# M405A.net
KiCad netlist of a schematic drawn in EAGLE
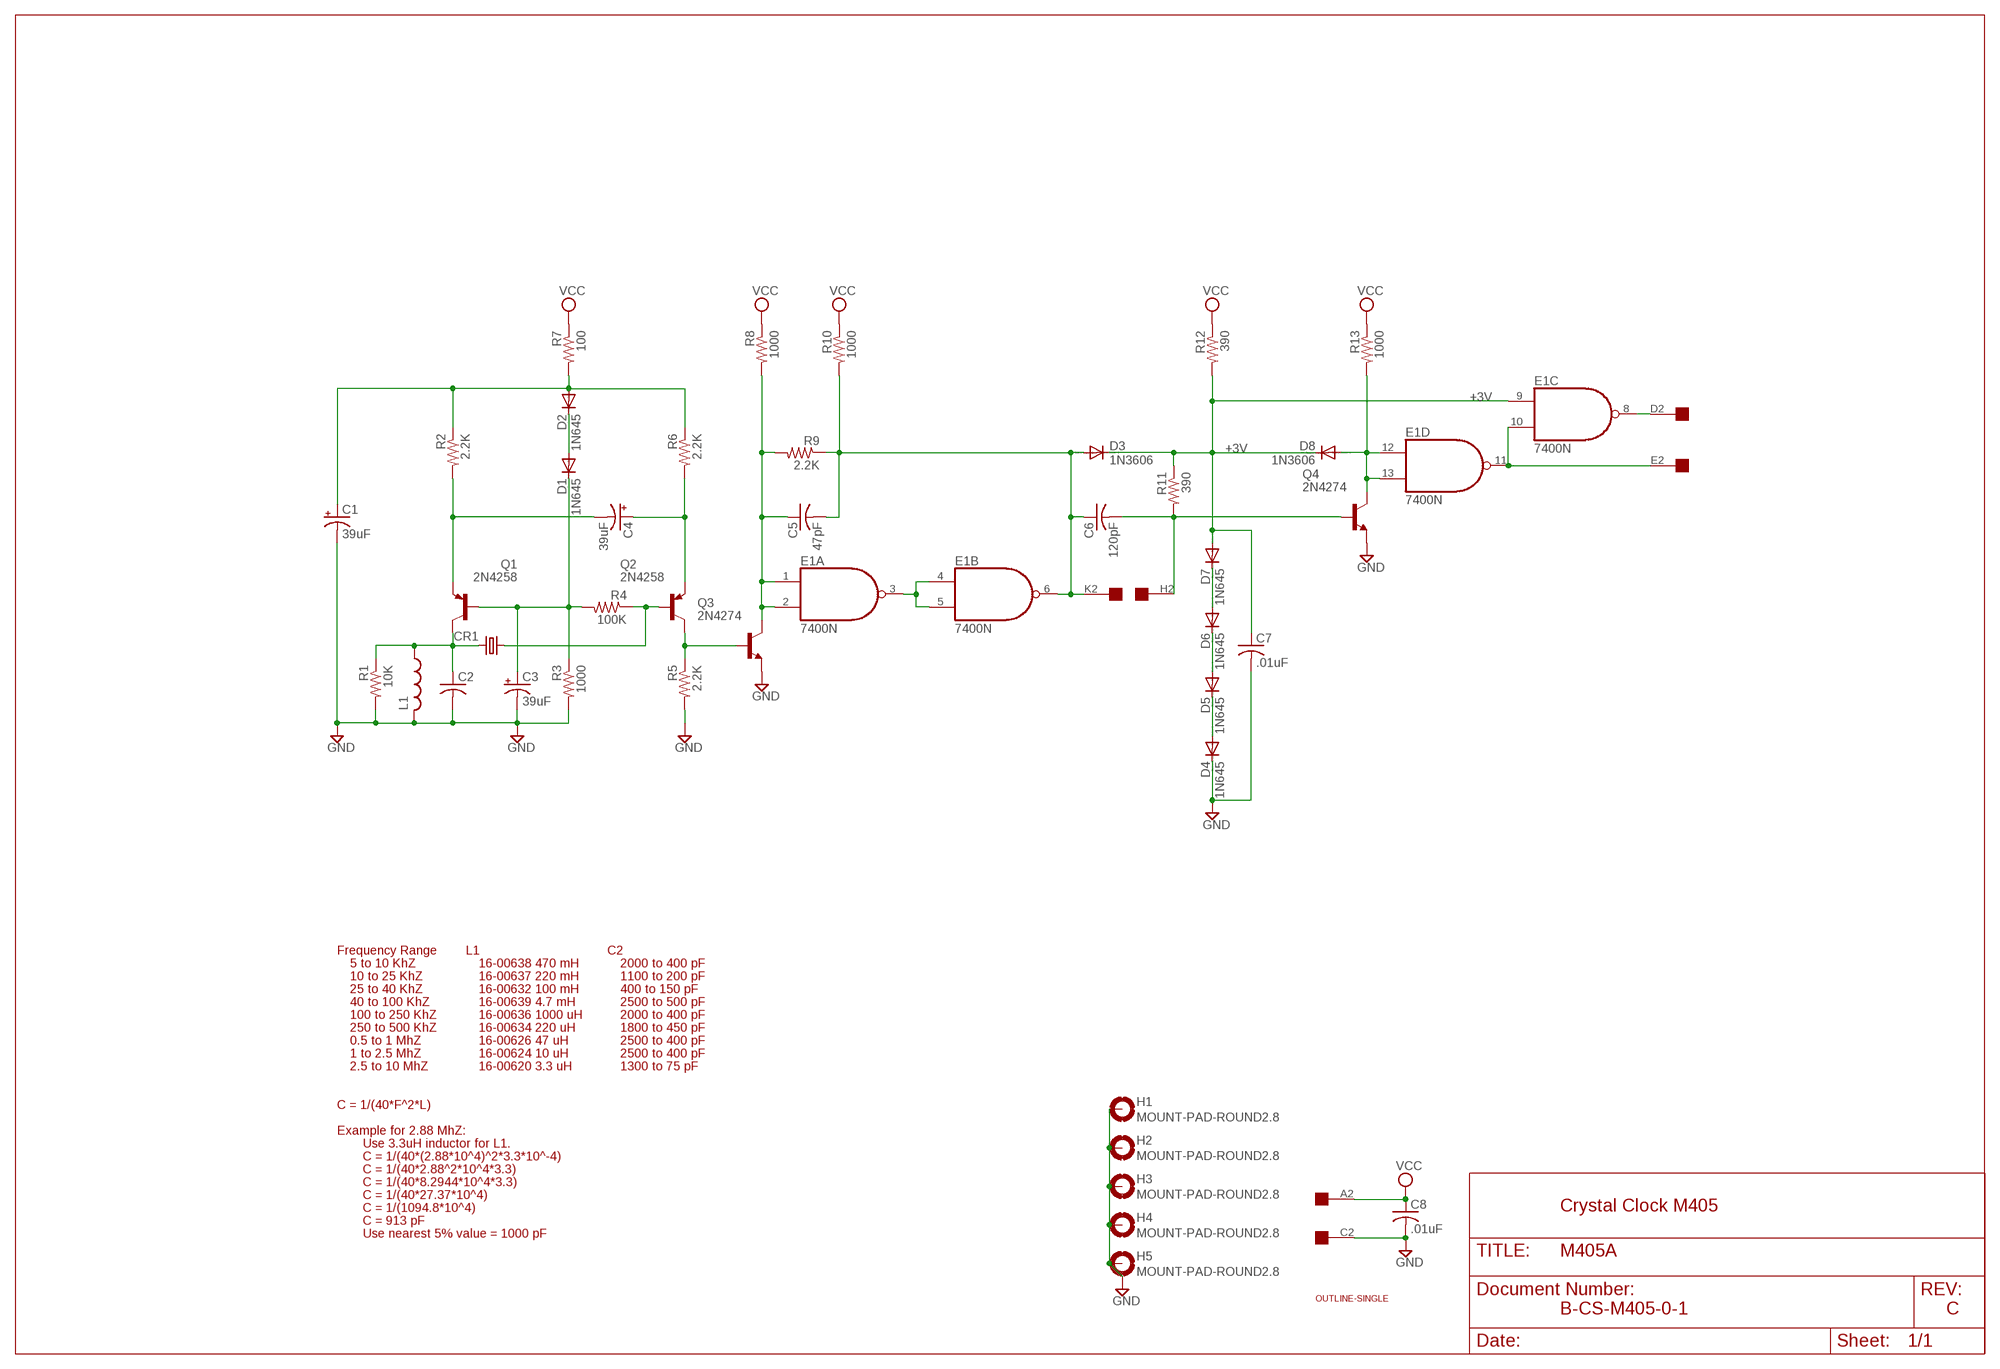
[diagram p0: schematic, sheet 1]

(export (version "E")
  (design (tool "Eeschema 10.0.6"))
  (components
    (comp (ref "C1")
      (value "39uF")
      (footprint "eagle-import:E15-5")
      (libsource (lib "eagle-import") (part "CPOL-USE15-5AXIAL"))
    )
    (comp (ref "C2")
      (value "C-US150-054X183")
      (footprint "eagle-import:C150-054X183")
      (libsource (lib "eagle-import") (part "C-US150-054X183"))
    )
    (comp (ref "C3")
      (value "39uF")
      (footprint "eagle-import:E15-5")
      (libsource (lib "eagle-import") (part "CPOL-USE15-5AXIAL"))
    )
    (comp (ref "C4")
      (value "39uF")
      (footprint "eagle-import:E15-5")
      (libsource (lib "eagle-import") (part "CPOL-USE15-5AXIAL"))
    )
    (comp (ref "C5")
      (value "47pF")
      (footprint "eagle-import:C050-025X075")
      (libsource (lib "eagle-import") (part "C-US050-025X075"))
    )
    (comp (ref "C6")
      (value "120pF")
      (footprint "eagle-import:C050-025X075")
      (libsource (lib "eagle-import") (part "C-US050-025X075"))
    )
    (comp (ref "C7")
      (value ".01uF")
      (footprint "eagle-import:C050-025X075")
      (libsource (lib "eagle-import") (part "C-US050-025X075"))
    )
    (comp (ref "C8")
      (value ".01uF")
      (footprint "eagle-import:C050-025X075")
      (libsource (lib "eagle-import") (part "C-US050-025X075"))
    )
    (comp (ref "CR1")
      (value "CRYSTALHC13U-H")
      (footprint "eagle-import:HC13U-H")
      (libsource (lib "eagle-import") (part "CRYSTALHC13U-H"))
    )
    (comp (ref "D1")
      (value "1N645")
      (footprint "eagle-import:DO35-10")
      (libsource (lib "eagle-import") (part "1N4148DO35-10"))
    )
    (comp (ref "D2")
      (value "1N645")
      (footprint "eagle-import:DO35-10")
      (libsource (lib "eagle-import") (part "1N4148DO35-10"))
    )
    (comp (ref "D3")
      (value "1N3606")
      (footprint "eagle-import:DO35-10")
      (libsource (lib "eagle-import") (part "1N4148DO35-10"))
    )
    (comp (ref "D4")
      (value "1N645")
      (footprint "eagle-import:DO35-10")
      (libsource (lib "eagle-import") (part "1N4148DO35-10"))
    )
    (comp (ref "D5")
      (value "1N645")
      (footprint "eagle-import:DO35-10")
      (libsource (lib "eagle-import") (part "1N4148DO35-10"))
    )
    (comp (ref "D6")
      (value "1N645")
      (footprint "eagle-import:DO35-10")
      (libsource (lib "eagle-import") (part "1N4148DO35-10"))
    )
    (comp (ref "D7")
      (value "1N645")
      (footprint "eagle-import:DO35-10")
      (libsource (lib "eagle-import") (part "1N4148DO35-10"))
    )
    (comp (ref "D8")
      (value "1N3606")
      (footprint "eagle-import:DO35-10")
      (libsource (lib "eagle-import") (part "1N4148DO35-10"))
    )
    (comp (ref "E1")
      (value "7400N")
      (footprint "eagle-import:DIL14")
      (libsource (lib "eagle-import") (part "7400N"))
    )
    (comp (ref "H1")
      (value "MOUNT-PAD-ROUND2.8")
      (footprint "eagle-import:2,8-PAD")
      (libsource (lib "eagle-import") (part "MOUNT-PAD-ROUND2.8"))
    )
    (comp (ref "H2")
      (value "MOUNT-PAD-ROUND2.8")
      (footprint "eagle-import:2,8-PAD")
      (libsource (lib "eagle-import") (part "MOUNT-PAD-ROUND2.8"))
    )
    (comp (ref "H3")
      (value "MOUNT-PAD-ROUND2.8")
      (footprint "eagle-import:2,8-PAD")
      (libsource (lib "eagle-import") (part "MOUNT-PAD-ROUND2.8"))
    )
    (comp (ref "H4")
      (value "MOUNT-PAD-ROUND2.8")
      (footprint "eagle-import:2,8-PAD")
      (libsource (lib "eagle-import") (part "MOUNT-PAD-ROUND2.8"))
    )
    (comp (ref "H5")
      (value "MOUNT-PAD-ROUND2.8")
      (footprint "eagle-import:2,8-PAD")
      (libsource (lib "eagle-import") (part "MOUNT-PAD-ROUND2.8"))
    )
    (comp (ref "L1")
      (value "L-US0207/12")
      (footprint "eagle-import:0207_12")
      (libsource (lib "eagle-import") (part "L-US0207/12"))
    )
    (comp (ref "Q1")
      (value "2N4258")
      (footprint "eagle-import:TO39")
      (libsource (lib "eagle-import") (part "-PNP-TO39-EBC2N3637"))
    )
    (comp (ref "Q2")
      (value "2N4258")
      (footprint "eagle-import:TO39")
      (libsource (lib "eagle-import") (part "-PNP-TO39-EBC2N3637"))
    )
    (comp (ref "Q3")
      (value "2N4274")
      (footprint "eagle-import:TO39")
      (libsource (lib "eagle-import") (part "-NPN-TO39-EBC2N3019"))
    )
    (comp (ref "Q4")
      (value "2N4274")
      (footprint "eagle-import:TO39")
      (libsource (lib "eagle-import") (part "-NPN-TO39-EBC2N3019"))
    )
    (comp (ref "R1")
      (value "10K")
      (footprint "eagle-import:0207_10")
      (libsource (lib "eagle-import") (part "R-US_0207/10"))
    )
    (comp (ref "R2")
      (value "2.2K")
      (footprint "eagle-import:0207_10")
      (libsource (lib "eagle-import") (part "R-US_0207/10"))
    )
    (comp (ref "R3")
      (value "1000")
      (footprint "eagle-import:0207_10")
      (libsource (lib "eagle-import") (part "R-US_0207/10"))
    )
    (comp (ref "R4")
      (value "100K")
      (footprint "eagle-import:0207_10")
      (libsource (lib "eagle-import") (part "R-US_0207/10"))
    )
    (comp (ref "R5")
      (value "2.2K")
      (footprint "eagle-import:0207_10")
      (libsource (lib "eagle-import") (part "R-US_0207/10"))
    )
    (comp (ref "R6")
      (value "2.2K")
      (footprint "eagle-import:0207_10")
      (libsource (lib "eagle-import") (part "R-US_0207/10"))
    )
    (comp (ref "R7")
      (value "100")
      (footprint "eagle-import:0207_10")
      (libsource (lib "eagle-import") (part "R-US_0207/10"))
    )
    (comp (ref "R8")
      (value "1000")
      (footprint "eagle-import:0207_10")
      (libsource (lib "eagle-import") (part "R-US_0207/10"))
    )
    (comp (ref "R9")
      (value "2.2K")
      (footprint "eagle-import:0207_10")
      (libsource (lib "eagle-import") (part "R-US_0207/10"))
    )
    (comp (ref "R10")
      (value "1000")
      (footprint "eagle-import:0207_10")
      (libsource (lib "eagle-import") (part "R-US_0207/10"))
    )
    (comp (ref "R11")
      (value "390")
      (footprint "eagle-import:0207_10")
      (libsource (lib "eagle-import") (part "R-US_0207/10"))
    )
    (comp (ref "R12")
      (value "390")
      (footprint "eagle-import:0207_10")
      (libsource (lib "eagle-import") (part "R-US_0207/10"))
    )
    (comp (ref "R13")
      (value "1000")
      (footprint "eagle-import:0207_10")
      (libsource (lib "eagle-import") (part "R-US_0207/10"))
    )
    (comp (ref "U$1")
      (value "OUTLINE-SINGLE")
      (footprint "eagle-import:SINGLE")
      (libsource (lib "eagle-import") (part "OUTLINE-SINGLE"))
    )
    (comp (ref "U$2")
      (value "EDGE-1")
      (footprint "eagle-import:EDGE-CON1")
      (libsource (lib "eagle-import") (part "EDGE-1"))
    )
  )
  (nets
    (net (code "1") (name "/+3V") (class "Default")
      (node (ref "C7") (pin "1") (pinfunction "1_1") (pintype "passive"))
      (node (ref "D3") (pin "C") (pinfunction "C_C") (pintype "passive"))
      (node (ref "D7") (pin "A") (pinfunction "A_A") (pintype "passive"))
      (node (ref "D8") (pin "C") (pinfunction "C_C") (pintype "passive"))
      (node (ref "E1") (pin "9") (pinfunction "I0_9") (pintype "input"))
      (node (ref "R11") (pin "1") (pinfunction "1_1") (pintype "passive"))
      (node (ref "R12") (pin "2") (pinfunction "2_2") (pintype "passive"))
    )
    (net (code "2") (name "GND") (class "Default")
      (node (ref "C1") (pin "-") (pinfunction "-_-") (pintype "passive"))
      (node (ref "C2") (pin "2") (pinfunction "2_2") (pintype "passive"))
      (node (ref "C3") (pin "-") (pinfunction "-_-") (pintype "passive"))
      (node (ref "C7") (pin "2") (pinfunction "2_2") (pintype "passive"))
      (node (ref "C8") (pin "2") (pinfunction "2_2") (pintype "passive"))
      (node (ref "D4") (pin "C") (pinfunction "C_C") (pintype "passive"))
      (node (ref "H1") (pin "B2,8") (pinfunction "MOUNT_B2,8") (pintype "passive"))
      (node (ref "H2") (pin "B2,8") (pinfunction "MOUNT_B2,8") (pintype "passive"))
      (node (ref "H3") (pin "B2,8") (pinfunction "MOUNT_B2,8") (pintype "passive"))
      (node (ref "H4") (pin "B2,8") (pinfunction "MOUNT_B2,8") (pintype "passive"))
      (node (ref "H5") (pin "B2,8") (pinfunction "MOUNT_B2,8") (pintype "passive"))
      (node (ref "L1") (pin "2") (pinfunction "2_2") (pintype "passive"))
      (node (ref "Q3") (pin "1") (pinfunction "E_1") (pintype "passive"))
      (node (ref "Q4") (pin "1") (pinfunction "E_1") (pintype "passive"))
      (node (ref "R1") (pin "2") (pinfunction "2_2") (pintype "passive"))
      (node (ref "R3") (pin "2") (pinfunction "2_2") (pintype "passive"))
      (node (ref "R5") (pin "2") (pinfunction "2_2") (pintype "passive"))
      (node (ref "U$2") (pin "C2") (pinfunction "1_C2") (pintype "bidirectional"))
    )
    (net (code "3") (name "Net-(C1-Pad+)") (class "Default")
      (node (ref "C1") (pin "+") (pinfunction "+_+") (pintype "passive"))
      (node (ref "D2") (pin "A") (pinfunction "A_A") (pintype "passive"))
      (node (ref "R2") (pin "1") (pinfunction "1_1") (pintype "passive"))
      (node (ref "R6") (pin "1") (pinfunction "1_1") (pintype "passive"))
      (node (ref "R7") (pin "2") (pinfunction "2_2") (pintype "passive"))
    )
    (net (code "4") (name "Net-(D1-PadA)") (class "Default")
      (node (ref "D1") (pin "A") (pinfunction "A_A") (pintype "passive"))
      (node (ref "D2") (pin "C") (pinfunction "C_C") (pintype "passive"))
    )
    (net (code "5") (name "Net-(D4-PadA)") (class "Default")
      (node (ref "D4") (pin "A") (pinfunction "A_A") (pintype "passive"))
      (node (ref "D5") (pin "C") (pinfunction "C_C") (pintype "passive"))
    )
    (net (code "6") (name "Net-(D5-PadA)") (class "Default")
      (node (ref "D5") (pin "A") (pinfunction "A_A") (pintype "passive"))
      (node (ref "D6") (pin "C") (pinfunction "C_C") (pintype "passive"))
    )
    (net (code "7") (name "Net-(D6-PadA)") (class "Default")
      (node (ref "D6") (pin "A") (pinfunction "A_A") (pintype "passive"))
      (node (ref "D7") (pin "C") (pinfunction "C_C") (pintype "passive"))
    )
    (net (code "8") (name "Net-(E1A-I0)") (class "Default")
      (node (ref "C5") (pin "1") (pinfunction "1_1") (pintype "passive"))
      (node (ref "E1") (pin "1") (pinfunction "I0_1") (pintype "input"))
      (node (ref "E1") (pin "2") (pinfunction "I1_2") (pintype "input"))
      (node (ref "Q3") (pin "3") (pinfunction "C_3") (pintype "passive"))
      (node (ref "R8") (pin "2") (pinfunction "2_2") (pintype "passive"))
      (node (ref "R9") (pin "2") (pinfunction "2_2") (pintype "passive"))
    )
    (net (code "9") (name "Net-(E1A-O)") (class "Default")
      (node (ref "E1") (pin "3") (pinfunction "O_3") (pintype "output"))
      (node (ref "E1") (pin "4") (pinfunction "I0_4") (pintype "input"))
      (node (ref "E1") (pin "5") (pinfunction "I1_5") (pintype "input"))
    )
    (net (code "10") (name "Net-(E1B-O)") (class "Default")
      (node (ref "C5") (pin "2") (pinfunction "2_2") (pintype "passive"))
      (node (ref "C6") (pin "1") (pinfunction "1_1") (pintype "passive"))
      (node (ref "D3") (pin "A") (pinfunction "A_A") (pintype "passive"))
      (node (ref "E1") (pin "6") (pinfunction "O_6") (pintype "output"))
      (node (ref "R10") (pin "2") (pinfunction "2_2") (pintype "passive"))
      (node (ref "R9") (pin "1") (pinfunction "1_1") (pintype "passive"))
      (node (ref "U$2") (pin "K2") (pinfunction "1_K2") (pintype "bidirectional"))
    )
    (net (code "11") (name "Net-(E1C-I1)") (class "Default")
      (node (ref "E1") (pin "10") (pinfunction "I1_10") (pintype "input"))
      (node (ref "E1") (pin "11") (pinfunction "O_11") (pintype "output"))
      (node (ref "U$2") (pin "E2") (pinfunction "1_E2") (pintype "bidirectional"))
    )
    (net (code "12") (name "Net-(E1C-O)") (class "Default")
      (node (ref "E1") (pin "8") (pinfunction "O_8") (pintype "output"))
      (node (ref "U$2") (pin "D2") (pinfunction "1_D2") (pintype "bidirectional"))
    )
    (net (code "13") (name "Net-(E1D-I0)") (class "Default")
      (node (ref "D8") (pin "A") (pinfunction "A_A") (pintype "passive"))
      (node (ref "E1") (pin "12") (pinfunction "I0_12") (pintype "input"))
      (node (ref "E1") (pin "13") (pinfunction "I1_13") (pintype "input"))
      (node (ref "Q4") (pin "3") (pinfunction "C_3") (pintype "passive"))
      (node (ref "R13") (pin "2") (pinfunction "2_2") (pintype "passive"))
    )
    (net (code "14") (name "Net-(Q1-B)") (class "Default")
      (node (ref "C3") (pin "+") (pinfunction "+_+") (pintype "passive"))
      (node (ref "D1") (pin "C") (pinfunction "C_C") (pintype "passive"))
      (node (ref "Q1") (pin "2") (pinfunction "B_2") (pintype "passive"))
      (node (ref "R3") (pin "1") (pinfunction "1_1") (pintype "passive"))
      (node (ref "R4") (pin "2") (pinfunction "2_2") (pintype "passive"))
    )
    (net (code "15") (name "Net-(Q1-C)") (class "Default")
      (node (ref "C2") (pin "1") (pinfunction "1_1") (pintype "passive"))
      (node (ref "CR1") (pin "2") (pinfunction "2_2") (pintype "passive"))
      (node (ref "L1") (pin "1") (pinfunction "1_1") (pintype "passive"))
      (node (ref "Q1") (pin "3") (pinfunction "C_3") (pintype "passive"))
      (node (ref "R1") (pin "1") (pinfunction "1_1") (pintype "passive"))
    )
    (net (code "16") (name "Net-(Q1-E)") (class "Default")
      (node (ref "C4") (pin "-") (pinfunction "-_-") (pintype "passive"))
      (node (ref "Q1") (pin "1") (pinfunction "E_1") (pintype "passive"))
      (node (ref "R2") (pin "2") (pinfunction "2_2") (pintype "passive"))
    )
    (net (code "17") (name "Net-(Q2-B)") (class "Default")
      (node (ref "CR1") (pin "1") (pinfunction "1_1") (pintype "passive"))
      (node (ref "Q2") (pin "2") (pinfunction "B_2") (pintype "passive"))
      (node (ref "R4") (pin "1") (pinfunction "1_1") (pintype "passive"))
    )
    (net (code "18") (name "Net-(Q2-C)") (class "Default")
      (node (ref "Q2") (pin "3") (pinfunction "C_3") (pintype "passive"))
      (node (ref "Q3") (pin "2") (pinfunction "B_2") (pintype "passive"))
      (node (ref "R5") (pin "1") (pinfunction "1_1") (pintype "passive"))
    )
    (net (code "19") (name "Net-(Q2-E)") (class "Default")
      (node (ref "C4") (pin "+") (pinfunction "+_+") (pintype "passive"))
      (node (ref "Q2") (pin "1") (pinfunction "E_1") (pintype "passive"))
      (node (ref "R6") (pin "2") (pinfunction "2_2") (pintype "passive"))
    )
    (net (code "20") (name "Net-(Q4-B)") (class "Default")
      (node (ref "C6") (pin "2") (pinfunction "2_2") (pintype "passive"))
      (node (ref "Q4") (pin "2") (pinfunction "B_2") (pintype "passive"))
      (node (ref "R11") (pin "2") (pinfunction "2_2") (pintype "passive"))
      (node (ref "U$2") (pin "H2") (pinfunction "1_H2") (pintype "bidirectional"))
    )
    (net (code "21") (name "VCC") (class "Default")
      (node (ref "C8") (pin "1") (pinfunction "1_1") (pintype "passive"))
      (node (ref "R10") (pin "1") (pinfunction "1_1") (pintype "passive"))
      (node (ref "R12") (pin "1") (pinfunction "1_1") (pintype "passive"))
      (node (ref "R13") (pin "1") (pinfunction "1_1") (pintype "passive"))
      (node (ref "R7") (pin "1") (pinfunction "1_1") (pintype "passive"))
      (node (ref "R8") (pin "1") (pinfunction "1_1") (pintype "passive"))
      (node (ref "U$2") (pin "A2") (pinfunction "1_A2") (pintype "bidirectional"))
    )
  )
)
